# 01_-_Stepper_Motor_Driver.net
KiCad netlist of a schematic drawn in Altium Designer
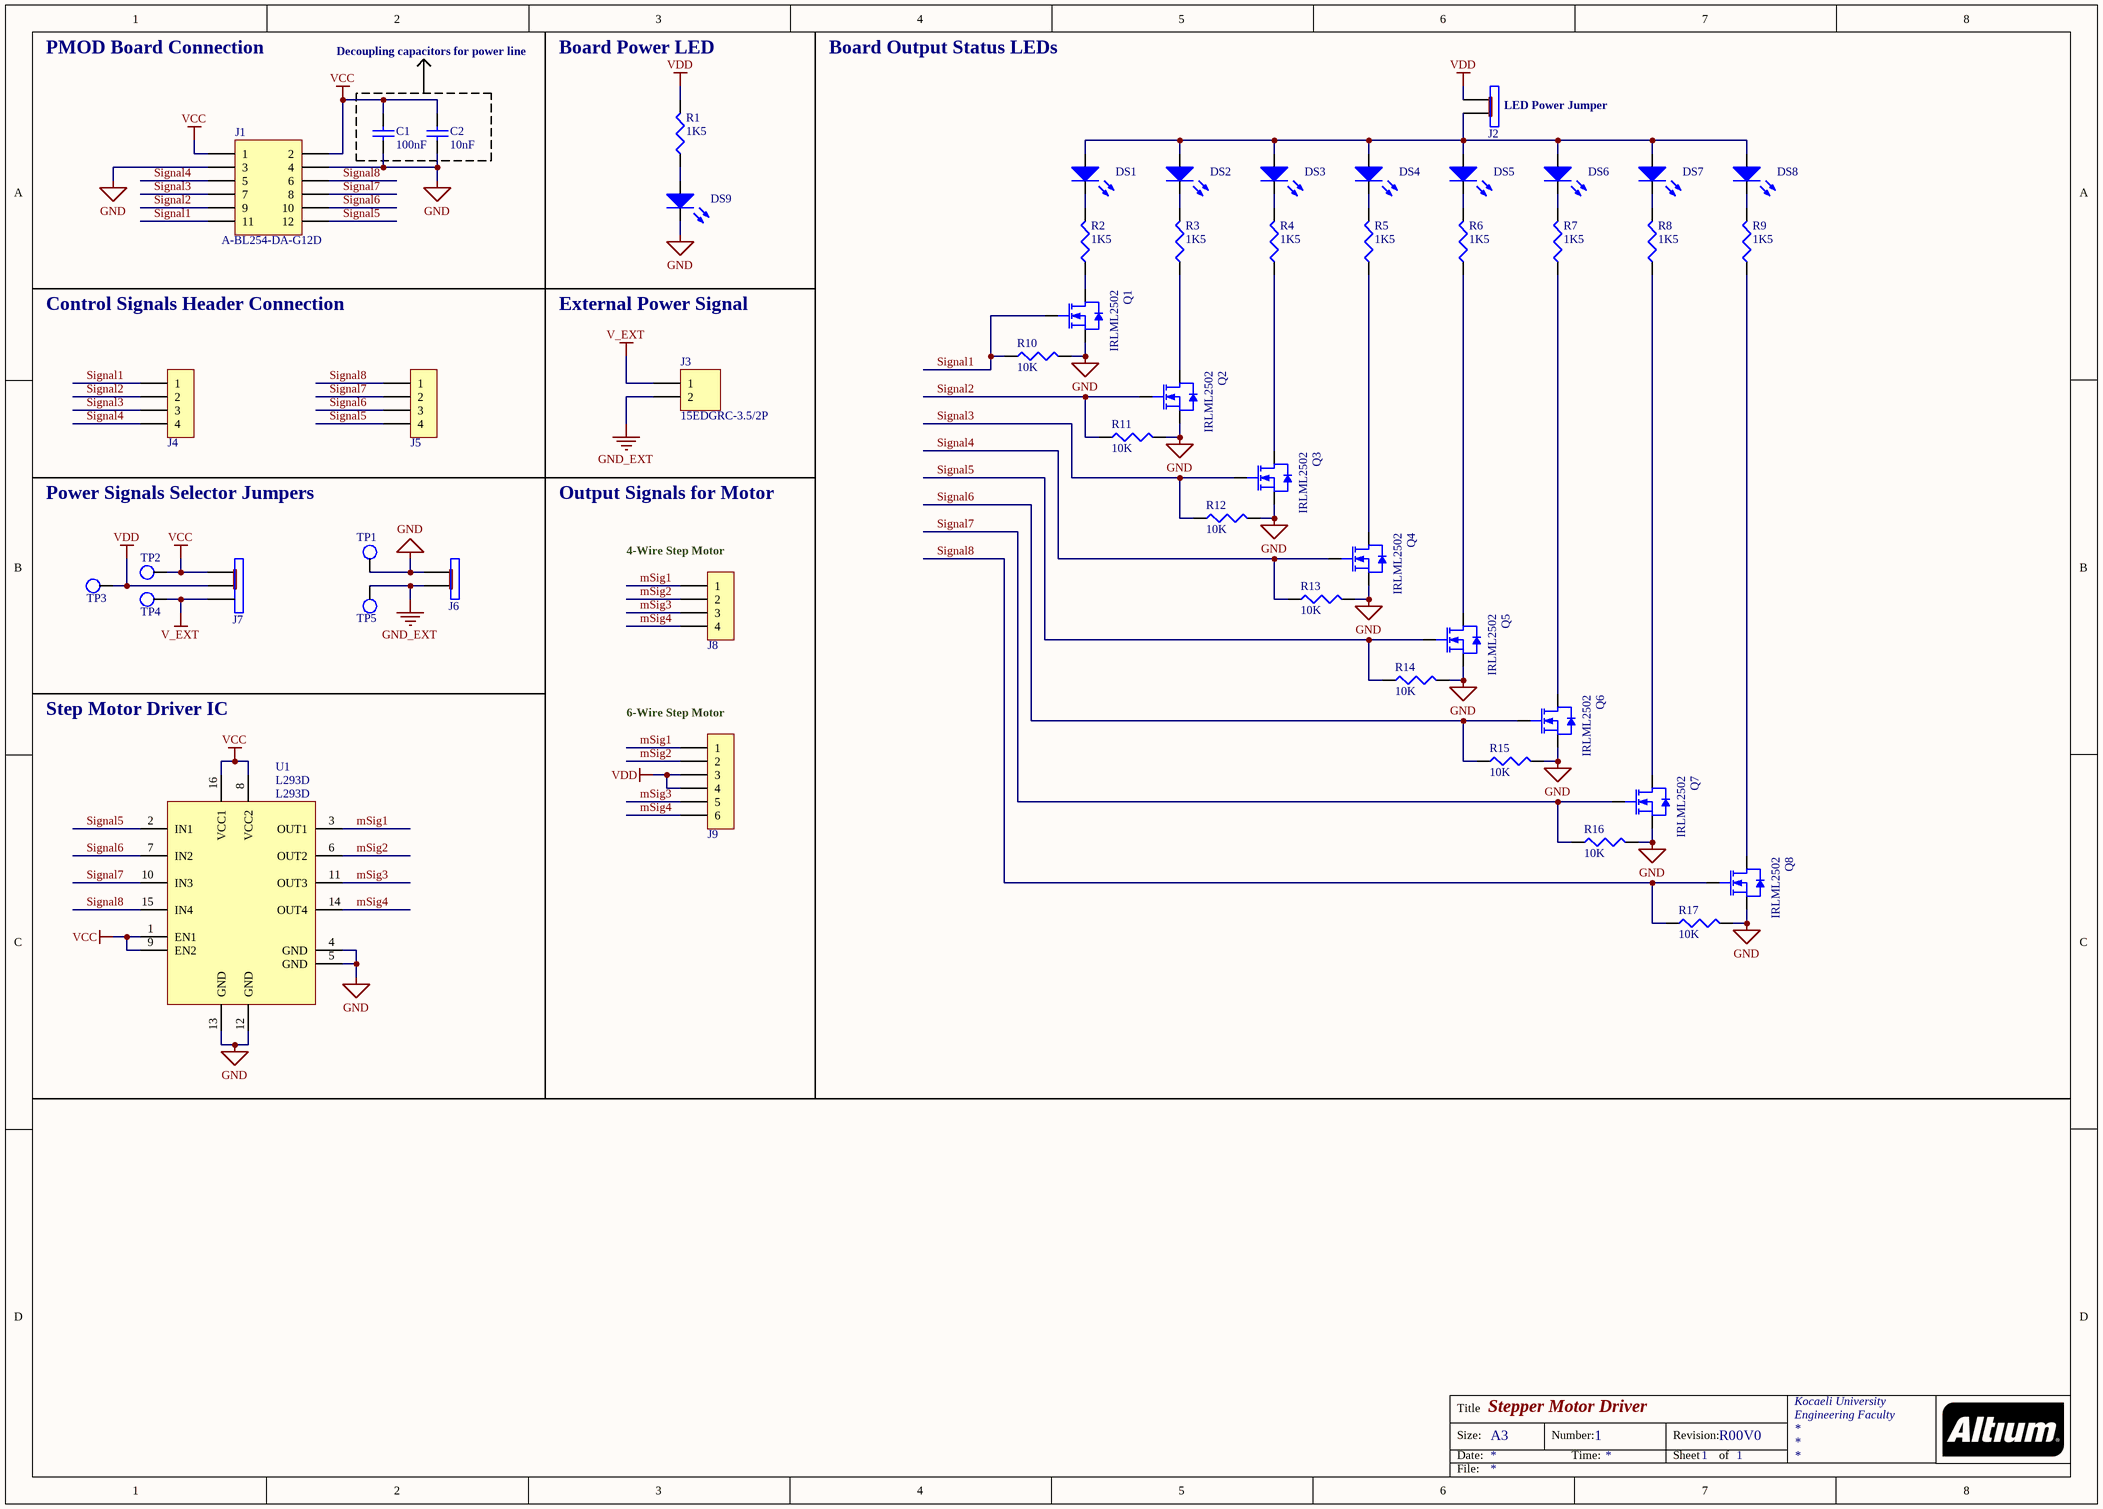
[diagram p0: [01] - Stepper Motor Driver.SchDoc]

(export (version "E")
  (design (tool "Eeschema 10.0.6"))
  (components
    (comp (ref "C1")
      (value "100nF")
      (footprint "CAP-0603")
      (description "CAP CER 0.1UF 50V 10% X7R 0603")
      (fields
        (field (name "MANUFACTURER") "Samsung Electro-Mechanics America, Inc")
        (field (name "MANUFACTURER PART NUMBER") "CL10B104KB8NNNC")
      )
      (libsource (lib "ykLibrary") (part "CAP-100N-0603"))
    )
    (comp (ref "C2")
      (value "10nF")
      (footprint "CAP-0603")
      (description "CAP CER 10000PF 50V 10% X7R 0603")
      (fields
        (field (name "MANUFACTURER") "Samsung Electro-Mechanics America, Inc")
        (field (name "MANUFACTURER PART NUMBER") "CL10B103KB8NNNC")
      )
      (libsource (lib "ykLibrary") (part "CAP-10N-0603"))
    )
    (comp (ref "DS1")
      (value "SMD Green Led")
      (footprint "LED_SMD_0603G")
      (description "LED GREEN CLEAR 0603 SMD")
      (fields
        (field (name "MANUFACTURER") "Lite-On Inc.")
        (field (name "MANUFACTURER PART NUMBER") "LTST-C193KGKT-5A")
      )
      (libsource (lib "ykLibrary") (part "LED-SMD-GRN"))
    )
    (comp (ref "DS2")
      (value "SMD Green Led")
      (footprint "LED_SMD_0603G")
      (description "LED GREEN CLEAR 0603 SMD")
      (fields
        (field (name "MANUFACTURER") "Lite-On Inc.")
        (field (name "MANUFACTURER PART NUMBER") "LTST-C193KGKT-5A")
      )
      (libsource (lib "ykLibrary") (part "LED-SMD-GRN"))
    )
    (comp (ref "DS3")
      (value "SMD Green Led")
      (footprint "LED_SMD_0603G")
      (description "LED GREEN CLEAR 0603 SMD")
      (fields
        (field (name "MANUFACTURER") "Lite-On Inc.")
        (field (name "MANUFACTURER PART NUMBER") "LTST-C193KGKT-5A")
      )
      (libsource (lib "ykLibrary") (part "LED-SMD-GRN"))
    )
    (comp (ref "DS4")
      (value "SMD Green Led")
      (footprint "LED_SMD_0603G")
      (description "LED GREEN CLEAR 0603 SMD")
      (fields
        (field (name "MANUFACTURER") "Lite-On Inc.")
        (field (name "MANUFACTURER PART NUMBER") "LTST-C193KGKT-5A")
      )
      (libsource (lib "ykLibrary") (part "LED-SMD-GRN"))
    )
    (comp (ref "DS5")
      (value "SMD Green Led")
      (footprint "LED_SMD_0603G")
      (description "LED GREEN CLEAR 0603 SMD")
      (fields
        (field (name "MANUFACTURER") "Lite-On Inc.")
        (field (name "MANUFACTURER PART NUMBER") "LTST-C193KGKT-5A")
      )
      (libsource (lib "ykLibrary") (part "LED-SMD-GRN"))
    )
    (comp (ref "DS6")
      (value "SMD Green Led")
      (footprint "LED_SMD_0603G")
      (description "LED GREEN CLEAR 0603 SMD")
      (fields
        (field (name "MANUFACTURER") "Lite-On Inc.")
        (field (name "MANUFACTURER PART NUMBER") "LTST-C193KGKT-5A")
      )
      (libsource (lib "ykLibrary") (part "LED-SMD-GRN"))
    )
    (comp (ref "DS7")
      (value "SMD Green Led")
      (footprint "LED_SMD_0603G")
      (description "LED GREEN CLEAR 0603 SMD")
      (fields
        (field (name "MANUFACTURER") "Lite-On Inc.")
        (field (name "MANUFACTURER PART NUMBER") "LTST-C193KGKT-5A")
      )
      (libsource (lib "ykLibrary") (part "LED-SMD-GRN"))
    )
    (comp (ref "DS8")
      (value "SMD Green Led")
      (footprint "LED_SMD_0603G")
      (description "LED GREEN CLEAR 0603 SMD")
      (fields
        (field (name "MANUFACTURER") "Lite-On Inc.")
        (field (name "MANUFACTURER PART NUMBER") "LTST-C193KGKT-5A")
      )
      (libsource (lib "ykLibrary") (part "LED-SMD-GRN"))
    )
    (comp (ref "DS9")
      (value "SMD Green Led")
      (footprint "LED_SMD_0603G")
      (description "LED GREEN CLEAR 0603 SMD")
      (fields
        (field (name "MANUFACTURER") "Lite-On Inc.")
        (field (name "MANUFACTURER PART NUMBER") "LTST-C193KGKT-5A")
      )
      (libsource (lib "ykLibrary") (part "LED-SMD-GRN"))
    )
    (comp (ref "J1")
      (value "A-BL254-DA-G12D")
      (footprint "CON-PMOD-FEMALE-2X6")
      (description "2.54mm Standart Female PMOD Connector 2x6")
      (fields (field (name "MANUFACTURER") "ASSMANN"))
      (libsource (lib "ykLibrary") (part "CON-PMOD-FEMALE-2X6"))
    )
    (comp (ref "J2")
      (value "2.54mm-Jumper")
      (footprint "CON-JUMPER-2.54-2L")
      (description "2.54mm Male Straight 1x2 standard Header")
      (fields (field (name "MANUFACTURER") "KLS"))
      (libsource (lib "ykLibrary") (part "CON-JUMPER-2.54-2L"))
    )
    (comp (ref "J3")
      (value "15EDGRC-3.5/2P")
      (footprint "15EDGRC-3.5-2")
      (description "Pluggable terminal block; socket; male; angled 90°; 3.5mm; ways:2")
      (fields (field (name "MANUFACTURER") "DEGSON ELECTRONICS"))
      (libsource (lib "ykLibrary") (part "15EDGRC-3.5-02P"))
    )
    (comp (ref "J4")
      (value "2.54mm-STD-M-1x4")
      (footprint "CON-HDR-M-2.54-1x4")
      (description "2.54mm Male Straight 1x2 standard Header")
      (fields (field (name "MANUFACTURER") "KLS"))
      (libsource (lib "ykLibrary") (part "CON-HDR-M-2.54-1x4"))
    )
    (comp (ref "J5")
      (value "2.54mm-STD-M-1x4")
      (footprint "CON-HDR-M-2.54-1x4")
      (description "2.54mm Male Straight 1x2 standard Header")
      (fields (field (name "MANUFACTURER") "KLS"))
      (libsource (lib "ykLibrary") (part "CON-HDR-M-2.54-1x4"))
    )
    (comp (ref "J6")
      (value "2.54mm-Jumper")
      (footprint "CON-JUMPER-2.54-2L")
      (description "2.54mm Male Straight 1x2 standard Header")
      (fields (field (name "MANUFACTURER") "KLS"))
      (libsource (lib "ykLibrary") (part "CON-JUMPER-2.54-2L"))
    )
    (comp (ref "J7")
      (value "2.54mm-Jumper")
      (footprint "CON-JUMPER-2.54-3L")
      (description "2.54mm Male Straight 1x2 standard Header")
      (fields (field (name "MANUFACTURER") "KLS"))
      (libsource (lib "ykLibrary") (part "CON-JUMPER-2.54-3L"))
    )
    (comp (ref "J8")
      (value "L-KLS1-XL5-2.50-04-R1")
      (footprint "CON-JST-XH-2.50-4PIN")
      (description "2.50mm JST-XH 4 Pin Male Connector")
      (fields (field (name "MANUFACTURER") "KLS Electronics"))
      (libsource (lib "ykLibrary") (part "CON-JST-XH-4PIN"))
    )
    (comp (ref "J9")
      (value "L-KLS1-XL5-2.50-06-R1")
      (footprint "CON-JST-XH-2.50-6PIN")
      (description "2.50mm JST-XH 6 Pin Male Connector")
      (fields (field (name "MANUFACTURER") "KLS Electronics"))
      (libsource (lib "ykLibrary") (part "CON-JST-XH-6PIN"))
    )
    (comp (ref "Q1")
      (value "IRLML2502")
      (footprint "SOT23_L")
      (description "MOSFET N-CH 20V 4.2A SOT23")
      (fields
        (field (name "MANUFACTURER") "Infineon Technologies")
        (field (name "MANUFACTURER PART NUMBER") "2N7002K")
      )
      (libsource (lib "ykLibrary") (part "TRQ-IRLML2502"))
    )
    (comp (ref "Q2")
      (value "IRLML2502")
      (footprint "SOT23_L")
      (description "MOSFET N-CH 20V 4.2A SOT23")
      (fields
        (field (name "MANUFACTURER") "Infineon Technologies")
        (field (name "MANUFACTURER PART NUMBER") "2N7002K")
      )
      (libsource (lib "ykLibrary") (part "TRQ-IRLML2502"))
    )
    (comp (ref "Q3")
      (value "IRLML2502")
      (footprint "SOT23_L")
      (description "MOSFET N-CH 20V 4.2A SOT23")
      (fields
        (field (name "MANUFACTURER") "Infineon Technologies")
        (field (name "MANUFACTURER PART NUMBER") "2N7002K")
      )
      (libsource (lib "ykLibrary") (part "TRQ-IRLML2502"))
    )
    (comp (ref "Q4")
      (value "IRLML2502")
      (footprint "SOT23_L")
      (description "MOSFET N-CH 20V 4.2A SOT23")
      (fields
        (field (name "MANUFACTURER") "Infineon Technologies")
        (field (name "MANUFACTURER PART NUMBER") "2N7002K")
      )
      (libsource (lib "ykLibrary") (part "TRQ-IRLML2502"))
    )
    (comp (ref "Q5")
      (value "IRLML2502")
      (footprint "SOT23_L")
      (description "MOSFET N-CH 20V 4.2A SOT23")
      (fields
        (field (name "MANUFACTURER") "Infineon Technologies")
        (field (name "MANUFACTURER PART NUMBER") "2N7002K")
      )
      (libsource (lib "ykLibrary") (part "TRQ-IRLML2502"))
    )
    (comp (ref "Q6")
      (value "IRLML2502")
      (footprint "SOT23_L")
      (description "MOSFET N-CH 20V 4.2A SOT23")
      (fields
        (field (name "MANUFACTURER") "Infineon Technologies")
        (field (name "MANUFACTURER PART NUMBER") "2N7002K")
      )
      (libsource (lib "ykLibrary") (part "TRQ-IRLML2502"))
    )
    (comp (ref "Q7")
      (value "IRLML2502")
      (footprint "SOT23_L")
      (description "MOSFET N-CH 20V 4.2A SOT23")
      (fields
        (field (name "MANUFACTURER") "Infineon Technologies")
        (field (name "MANUFACTURER PART NUMBER") "2N7002K")
      )
      (libsource (lib "ykLibrary") (part "TRQ-IRLML2502"))
    )
    (comp (ref "Q8")
      (value "IRLML2502")
      (footprint "SOT23_L")
      (description "MOSFET N-CH 20V 4.2A SOT23")
      (fields
        (field (name "MANUFACTURER") "Infineon Technologies")
        (field (name "MANUFACTURER PART NUMBER") "2N7002K")
      )
      (libsource (lib "ykLibrary") (part "TRQ-IRLML2502"))
    )
    (comp (ref "R1")
      (value "1K5")
      (footprint "RES-0603")
      (description "RES 1.5K OHM 1% 1/10W 0603")
      (fields
        (field (name "MANUFACTURER") "YAGEO")
        (field (name "MANUFACTURER PART NUMBER") "RC0603FR-131K5L")
      )
      (libsource (lib "ykLibrary") (part "RES-1K5-0603"))
    )
    (comp (ref "R2")
      (value "1K5")
      (footprint "RES-0603")
      (description "RES 1.5K OHM 1% 1/10W 0603")
      (fields
        (field (name "MANUFACTURER") "YAGEO")
        (field (name "MANUFACTURER PART NUMBER") "RC0603FR-131K5L")
      )
      (libsource (lib "ykLibrary") (part "RES-1K5-0603"))
    )
    (comp (ref "R3")
      (value "1K5")
      (footprint "RES-0603")
      (description "RES 1.5K OHM 1% 1/10W 0603")
      (fields
        (field (name "MANUFACTURER") "YAGEO")
        (field (name "MANUFACTURER PART NUMBER") "RC0603FR-131K5L")
      )
      (libsource (lib "ykLibrary") (part "RES-1K5-0603"))
    )
    (comp (ref "R4")
      (value "1K5")
      (footprint "RES-0603")
      (description "RES 1.5K OHM 1% 1/10W 0603")
      (fields
        (field (name "MANUFACTURER") "YAGEO")
        (field (name "MANUFACTURER PART NUMBER") "RC0603FR-131K5L")
      )
      (libsource (lib "ykLibrary") (part "RES-1K5-0603"))
    )
    (comp (ref "R5")
      (value "1K5")
      (footprint "RES-0603")
      (description "RES 1.5K OHM 1% 1/10W 0603")
      (fields
        (field (name "MANUFACTURER") "YAGEO")
        (field (name "MANUFACTURER PART NUMBER") "RC0603FR-131K5L")
      )
      (libsource (lib "ykLibrary") (part "RES-1K5-0603"))
    )
    (comp (ref "R6")
      (value "1K5")
      (footprint "RES-0603")
      (description "RES 1.5K OHM 1% 1/10W 0603")
      (fields
        (field (name "MANUFACTURER") "YAGEO")
        (field (name "MANUFACTURER PART NUMBER") "RC0603FR-131K5L")
      )
      (libsource (lib "ykLibrary") (part "RES-1K5-0603"))
    )
    (comp (ref "R7")
      (value "1K5")
      (footprint "RES-0603")
      (description "RES 1.5K OHM 1% 1/10W 0603")
      (fields
        (field (name "MANUFACTURER") "YAGEO")
        (field (name "MANUFACTURER PART NUMBER") "RC0603FR-131K5L")
      )
      (libsource (lib "ykLibrary") (part "RES-1K5-0603"))
    )
    (comp (ref "R8")
      (value "1K5")
      (footprint "RES-0603")
      (description "RES 1.5K OHM 1% 1/10W 0603")
      (fields
        (field (name "MANUFACTURER") "YAGEO")
        (field (name "MANUFACTURER PART NUMBER") "RC0603FR-131K5L")
      )
      (libsource (lib "ykLibrary") (part "RES-1K5-0603"))
    )
    (comp (ref "R9")
      (value "1K5")
      (footprint "RES-0603")
      (description "RES 1.5K OHM 1% 1/10W 0603")
      (fields
        (field (name "MANUFACTURER") "YAGEO")
        (field (name "MANUFACTURER PART NUMBER") "RC0603FR-131K5L")
      )
      (libsource (lib "ykLibrary") (part "RES-1K5-0603"))
    )
    (comp (ref "R10")
      (value "10K")
      (footprint "RES-0603")
      (description "RES 10K OHM 1% 1/10W 0603")
      (fields
        (field (name "MANUFACTURER") "YAGEO")
        (field (name "MANUFACTURER PART NUMBER") "RC0603FR-1310KL")
      )
      (libsource (lib "ykLibrary") (part "RES-10K-0603"))
    )
    (comp (ref "R11")
      (value "10K")
      (footprint "RES-0603")
      (description "RES 10K OHM 1% 1/10W 0603")
      (fields
        (field (name "MANUFACTURER") "YAGEO")
        (field (name "MANUFACTURER PART NUMBER") "RC0603FR-1310KL")
      )
      (libsource (lib "ykLibrary") (part "RES-10K-0603"))
    )
    (comp (ref "R12")
      (value "10K")
      (footprint "RES-0603")
      (description "RES 10K OHM 1% 1/10W 0603")
      (fields
        (field (name "MANUFACTURER") "YAGEO")
        (field (name "MANUFACTURER PART NUMBER") "RC0603FR-1310KL")
      )
      (libsource (lib "ykLibrary") (part "RES-10K-0603"))
    )
    (comp (ref "R13")
      (value "10K")
      (footprint "RES-0603")
      (description "RES 10K OHM 1% 1/10W 0603")
      (fields
        (field (name "MANUFACTURER") "YAGEO")
        (field (name "MANUFACTURER PART NUMBER") "RC0603FR-1310KL")
      )
      (libsource (lib "ykLibrary") (part "RES-10K-0603"))
    )
    (comp (ref "R14")
      (value "10K")
      (footprint "RES-0603")
      (description "RES 10K OHM 1% 1/10W 0603")
      (fields
        (field (name "MANUFACTURER") "YAGEO")
        (field (name "MANUFACTURER PART NUMBER") "RC0603FR-1310KL")
      )
      (libsource (lib "ykLibrary") (part "RES-10K-0603"))
    )
    (comp (ref "R15")
      (value "10K")
      (footprint "RES-0603")
      (description "RES 10K OHM 1% 1/10W 0603")
      (fields
        (field (name "MANUFACTURER") "YAGEO")
        (field (name "MANUFACTURER PART NUMBER") "RC0603FR-1310KL")
      )
      (libsource (lib "ykLibrary") (part "RES-10K-0603"))
    )
    (comp (ref "R16")
      (value "10K")
      (footprint "RES-0603")
      (description "RES 10K OHM 1% 1/10W 0603")
      (fields
        (field (name "MANUFACTURER") "YAGEO")
        (field (name "MANUFACTURER PART NUMBER") "RC0603FR-1310KL")
      )
      (libsource (lib "ykLibrary") (part "RES-10K-0603"))
    )
    (comp (ref "R17")
      (value "10K")
      (footprint "RES-0603")
      (description "RES 10K OHM 1% 1/10W 0603")
      (fields
        (field (name "MANUFACTURER") "YAGEO")
        (field (name "MANUFACTURER PART NUMBER") "RC0603FR-1310KL")
      )
      (libsource (lib "ykLibrary") (part "RES-10K-0603"))
    )
    (comp (ref "TP1")
      (value "TP")
      (footprint "TP_TH")
      (description "Test Point")
      (fields (field (name "PUBLISHER") "tmk"))
      (libsource (lib "ykLibrary") (part "TP"))
    )
    (comp (ref "TP2")
      (value "TP")
      (footprint "TP_TH")
      (description "Test Point")
      (fields (field (name "PUBLISHER") "tmk"))
      (libsource (lib "ykLibrary") (part "TP"))
    )
    (comp (ref "TP3")
      (value "TP")
      (footprint "TP_TH")
      (description "Test Point")
      (fields (field (name "PUBLISHER") "tmk"))
      (libsource (lib "ykLibrary") (part "TP"))
    )
    (comp (ref "TP4")
      (value "TP")
      (footprint "TP_TH")
      (description "Test Point")
      (fields (field (name "PUBLISHER") "tmk"))
      (libsource (lib "ykLibrary") (part "TP"))
    )
    (comp (ref "TP5")
      (value "TP")
      (footprint "TP_TH")
      (description "Test Point")
      (fields (field (name "PUBLISHER") "tmk"))
      (libsource (lib "ykLibrary") (part "TP"))
    )
    (comp (ref "U1")
      (value "L293D")
      (footprint "PDIP-16")
      (description "IC MTR DRV BIPOLR 4.5-36V 20SOIC")
      (fields (field (name "ALTIUM_VALUE") "L293D"))
      (libsource (lib "ykLibrary") (part "IC-L293D-PDIP"))
    )
  )
  (nets
    (net (code "1") (name "/Signal1") (class "Default")
      (node (ref "J1") (pin "11") (pinfunction "11_11") (pintype "passive"))
      (node (ref "J4") (pin "1") (pinfunction "1_1") (pintype "passive"))
      (node (ref "Q1") (pin "1") (pinfunction "G_1") (pintype "passive"))
      (node (ref "R10") (pin "1") (pinfunction "1_1") (pintype "passive"))
    )
    (net (code "2") (name "/Signal2") (class "Default")
      (node (ref "J1") (pin "9") (pinfunction "9_9") (pintype "passive"))
      (node (ref "J4") (pin "2") (pinfunction "2_2") (pintype "passive"))
      (node (ref "Q2") (pin "1") (pinfunction "G_1") (pintype "passive"))
      (node (ref "R11") (pin "1") (pinfunction "1_1") (pintype "passive"))
    )
    (net (code "3") (name "/Signal3") (class "Default")
      (node (ref "J1") (pin "7") (pinfunction "7_7") (pintype "passive"))
      (node (ref "J4") (pin "3") (pinfunction "3_3") (pintype "passive"))
      (node (ref "Q3") (pin "1") (pinfunction "G_1") (pintype "passive"))
      (node (ref "R12") (pin "1") (pinfunction "1_1") (pintype "passive"))
    )
    (net (code "4") (name "/Signal4") (class "Default")
      (node (ref "J1") (pin "5") (pinfunction "5_5") (pintype "passive"))
      (node (ref "J4") (pin "4") (pinfunction "4_4") (pintype "passive"))
      (node (ref "Q4") (pin "1") (pinfunction "G_1") (pintype "passive"))
      (node (ref "R13") (pin "1") (pinfunction "1_1") (pintype "passive"))
    )
    (net (code "5") (name "/Signal5") (class "Default")
      (node (ref "J1") (pin "12") (pinfunction "12_12") (pintype "passive"))
      (node (ref "J5") (pin "4") (pinfunction "4_4") (pintype "passive"))
      (node (ref "Q5") (pin "1") (pinfunction "G_1") (pintype "passive"))
      (node (ref "R14") (pin "1") (pinfunction "1_1") (pintype "passive"))
      (node (ref "U1") (pin "2") (pinfunction "IN1_2") (pintype "passive"))
    )
    (net (code "6") (name "/Signal6") (class "Default")
      (node (ref "J1") (pin "10") (pinfunction "10_10") (pintype "passive"))
      (node (ref "J5") (pin "3") (pinfunction "3_3") (pintype "passive"))
      (node (ref "Q6") (pin "1") (pinfunction "G_1") (pintype "passive"))
      (node (ref "R15") (pin "1") (pinfunction "1_1") (pintype "passive"))
      (node (ref "U1") (pin "7") (pinfunction "IN2_7") (pintype "passive"))
    )
    (net (code "7") (name "/Signal7") (class "Default")
      (node (ref "J1") (pin "8") (pinfunction "8_8") (pintype "passive"))
      (node (ref "J5") (pin "2") (pinfunction "2_2") (pintype "passive"))
      (node (ref "Q7") (pin "1") (pinfunction "G_1") (pintype "passive"))
      (node (ref "R16") (pin "1") (pinfunction "1_1") (pintype "passive"))
      (node (ref "U1") (pin "10") (pinfunction "IN3_10") (pintype "passive"))
    )
    (net (code "8") (name "/Signal8") (class "Default")
      (node (ref "J1") (pin "6") (pinfunction "6_6") (pintype "passive"))
      (node (ref "J5") (pin "1") (pinfunction "1_1") (pintype "passive"))
      (node (ref "Q8") (pin "1") (pinfunction "G_1") (pintype "passive"))
      (node (ref "R17") (pin "1") (pinfunction "1_1") (pintype "passive"))
      (node (ref "U1") (pin "15") (pinfunction "IN4_15") (pintype "passive"))
    )
    (net (code "9") (name "/mSig1") (class "Default")
      (node (ref "J8") (pin "1") (pinfunction "1_1") (pintype "passive"))
      (node (ref "J9") (pin "1") (pinfunction "1_1") (pintype "passive"))
      (node (ref "U1") (pin "3") (pinfunction "OUT1_3") (pintype "passive"))
    )
    (net (code "10") (name "/mSig2") (class "Default")
      (node (ref "J8") (pin "2") (pinfunction "2_2") (pintype "passive"))
      (node (ref "J9") (pin "2") (pinfunction "2_2") (pintype "passive"))
      (node (ref "U1") (pin "6") (pinfunction "OUT2_6") (pintype "passive"))
    )
    (net (code "11") (name "/mSig3") (class "Default")
      (node (ref "J8") (pin "3") (pinfunction "3_3") (pintype "passive"))
      (node (ref "J9") (pin "5") (pinfunction "5_5") (pintype "passive"))
      (node (ref "U1") (pin "11") (pinfunction "OUT3_11") (pintype "passive"))
    )
    (net (code "12") (name "/mSig4") (class "Default")
      (node (ref "J8") (pin "4") (pinfunction "4_4") (pintype "passive"))
      (node (ref "J9") (pin "6") (pinfunction "6_6") (pintype "passive"))
      (node (ref "U1") (pin "14") (pinfunction "OUT4_14") (pintype "passive"))
    )
    (net (code "13") (name "GND") (class "Default")
      (node (ref "C1") (pin "1") (pinfunction "1_1") (pintype "passive"))
      (node (ref "C2") (pin "1") (pinfunction "1_1") (pintype "passive"))
      (node (ref "DS9") (pin "2") (pinfunction "K_2") (pintype "passive"))
      (node (ref "J1") (pin "3") (pinfunction "3_3") (pintype "passive"))
      (node (ref "J1") (pin "4") (pinfunction "4_4") (pintype "passive"))
      (node (ref "J6") (pin "1") (pinfunction "1_1") (pintype "passive"))
      (node (ref "Q1") (pin "2") (pinfunction "S_2") (pintype "passive"))
      (node (ref "Q2") (pin "2") (pinfunction "S_2") (pintype "passive"))
      (node (ref "Q3") (pin "2") (pinfunction "S_2") (pintype "passive"))
      (node (ref "Q4") (pin "2") (pinfunction "S_2") (pintype "passive"))
      (node (ref "Q5") (pin "2") (pinfunction "S_2") (pintype "passive"))
      (node (ref "Q6") (pin "2") (pinfunction "S_2") (pintype "passive"))
      (node (ref "Q7") (pin "2") (pinfunction "S_2") (pintype "passive"))
      (node (ref "Q8") (pin "2") (pinfunction "S_2") (pintype "passive"))
      (node (ref "R10") (pin "2") (pinfunction "2_2") (pintype "passive"))
      (node (ref "R11") (pin "2") (pinfunction "2_2") (pintype "passive"))
      (node (ref "R12") (pin "2") (pinfunction "2_2") (pintype "passive"))
      (node (ref "R13") (pin "2") (pinfunction "2_2") (pintype "passive"))
      (node (ref "R14") (pin "2") (pinfunction "2_2") (pintype "passive"))
      (node (ref "R15") (pin "2") (pinfunction "2_2") (pintype "passive"))
      (node (ref "R16") (pin "2") (pinfunction "2_2") (pintype "passive"))
      (node (ref "R17") (pin "2") (pinfunction "2_2") (pintype "passive"))
      (node (ref "TP1") (pin "0") (pinfunction "0_0") (pintype "passive"))
      (node (ref "U1") (pin "12") (pinfunction "GND_12") (pintype "passive"))
      (node (ref "U1") (pin "13") (pinfunction "GND_13") (pintype "passive"))
      (node (ref "U1") (pin "4") (pinfunction "GND_4") (pintype "passive"))
      (node (ref "U1") (pin "5") (pinfunction "GND_5") (pintype "passive"))
    )
    (net (code "14") (name "GND_EXT") (class "Default")
      (node (ref "J3") (pin "2") (pinfunction "2_2") (pintype "passive"))
      (node (ref "J6") (pin "2") (pinfunction "2_2") (pintype "passive"))
      (node (ref "TP5") (pin "0") (pinfunction "0_0") (pintype "passive"))
    )
    (net (code "15") (name "Net-(DS1-A)") (class "Default")
      (node (ref "DS1") (pin "1") (pinfunction "A_1") (pintype "passive"))
      (node (ref "DS2") (pin "1") (pinfunction "A_1") (pintype "passive"))
      (node (ref "DS3") (pin "1") (pinfunction "A_1") (pintype "passive"))
      (node (ref "DS4") (pin "1") (pinfunction "A_1") (pintype "passive"))
      (node (ref "DS5") (pin "1") (pinfunction "A_1") (pintype "passive"))
      (node (ref "DS6") (pin "1") (pinfunction "A_1") (pintype "passive"))
      (node (ref "DS7") (pin "1") (pinfunction "A_1") (pintype "passive"))
      (node (ref "DS8") (pin "1") (pinfunction "A_1") (pintype "passive"))
      (node (ref "J2") (pin "2") (pinfunction "2_2") (pintype "passive"))
    )
    (net (code "16") (name "Net-(DS1-K)") (class "Default")
      (node (ref "DS1") (pin "2") (pinfunction "K_2") (pintype "passive"))
      (node (ref "R2") (pin "2") (pinfunction "2_2") (pintype "passive"))
    )
    (net (code "17") (name "Net-(DS2-K)") (class "Default")
      (node (ref "DS2") (pin "2") (pinfunction "K_2") (pintype "passive"))
      (node (ref "R3") (pin "2") (pinfunction "2_2") (pintype "passive"))
    )
    (net (code "18") (name "Net-(DS3-K)") (class "Default")
      (node (ref "DS3") (pin "2") (pinfunction "K_2") (pintype "passive"))
      (node (ref "R4") (pin "2") (pinfunction "2_2") (pintype "passive"))
    )
    (net (code "19") (name "Net-(DS4-K)") (class "Default")
      (node (ref "DS4") (pin "2") (pinfunction "K_2") (pintype "passive"))
      (node (ref "R5") (pin "2") (pinfunction "2_2") (pintype "passive"))
    )
    (net (code "20") (name "Net-(DS5-K)") (class "Default")
      (node (ref "DS5") (pin "2") (pinfunction "K_2") (pintype "passive"))
      (node (ref "R6") (pin "2") (pinfunction "2_2") (pintype "passive"))
    )
    (net (code "21") (name "Net-(DS6-K)") (class "Default")
      (node (ref "DS6") (pin "2") (pinfunction "K_2") (pintype "passive"))
      (node (ref "R7") (pin "2") (pinfunction "2_2") (pintype "passive"))
    )
    (net (code "22") (name "Net-(DS7-K)") (class "Default")
      (node (ref "DS7") (pin "2") (pinfunction "K_2") (pintype "passive"))
      (node (ref "R8") (pin "2") (pinfunction "2_2") (pintype "passive"))
    )
    (net (code "23") (name "Net-(DS8-K)") (class "Default")
      (node (ref "DS8") (pin "2") (pinfunction "K_2") (pintype "passive"))
      (node (ref "R9") (pin "2") (pinfunction "2_2") (pintype "passive"))
    )
    (net (code "24") (name "Net-(DS9-A)") (class "Default")
      (node (ref "DS9") (pin "1") (pinfunction "A_1") (pintype "passive"))
      (node (ref "R1") (pin "1") (pinfunction "1_1") (pintype "passive"))
    )
    (net (code "25") (name "Net-(Q1-D)") (class "Default")
      (node (ref "Q1") (pin "3") (pinfunction "D_3") (pintype "passive"))
      (node (ref "R2") (pin "1") (pinfunction "1_1") (pintype "passive"))
    )
    (net (code "26") (name "Net-(Q2-D)") (class "Default")
      (node (ref "Q2") (pin "3") (pinfunction "D_3") (pintype "passive"))
      (node (ref "R3") (pin "1") (pinfunction "1_1") (pintype "passive"))
    )
    (net (code "27") (name "Net-(Q3-D)") (class "Default")
      (node (ref "Q3") (pin "3") (pinfunction "D_3") (pintype "passive"))
      (node (ref "R4") (pin "1") (pinfunction "1_1") (pintype "passive"))
    )
    (net (code "28") (name "Net-(Q4-D)") (class "Default")
      (node (ref "Q4") (pin "3") (pinfunction "D_3") (pintype "passive"))
      (node (ref "R5") (pin "1") (pinfunction "1_1") (pintype "passive"))
    )
    (net (code "29") (name "Net-(Q5-D)") (class "Default")
      (node (ref "Q5") (pin "3") (pinfunction "D_3") (pintype "passive"))
      (node (ref "R6") (pin "1") (pinfunction "1_1") (pintype "passive"))
    )
    (net (code "30") (name "Net-(Q6-D)") (class "Default")
      (node (ref "Q6") (pin "3") (pinfunction "D_3") (pintype "passive"))
      (node (ref "R7") (pin "1") (pinfunction "1_1") (pintype "passive"))
    )
    (net (code "31") (name "Net-(Q7-D)") (class "Default")
      (node (ref "Q7") (pin "3") (pinfunction "D_3") (pintype "passive"))
      (node (ref "R8") (pin "1") (pinfunction "1_1") (pintype "passive"))
    )
    (net (code "32") (name "Net-(Q8-D)") (class "Default")
      (node (ref "Q8") (pin "3") (pinfunction "D_3") (pintype "passive"))
      (node (ref "R9") (pin "1") (pinfunction "1_1") (pintype "passive"))
    )
    (net (code "33") (name "VCC") (class "Default")
      (node (ref "C1") (pin "2") (pinfunction "2_2") (pintype "passive"))
      (node (ref "C2") (pin "2") (pinfunction "2_2") (pintype "passive"))
      (node (ref "J1") (pin "1") (pinfunction "1_1") (pintype "passive"))
      (node (ref "J1") (pin "2") (pinfunction "2_2") (pintype "passive"))
      (node (ref "J7") (pin "1") (pinfunction "1_1") (pintype "passive"))
      (node (ref "TP2") (pin "0") (pinfunction "0_0") (pintype "passive"))
      (node (ref "U1") (pin "1") (pinfunction "EN1_1") (pintype "passive"))
      (node (ref "U1") (pin "16") (pinfunction "VCC1_16") (pintype "passive"))
      (node (ref "U1") (pin "8") (pinfunction "VCC2_8") (pintype "passive"))
      (node (ref "U1") (pin "9") (pinfunction "EN2_9") (pintype "passive"))
    )
    (net (code "34") (name "VDD") (class "Default")
      (node (ref "J2") (pin "1") (pinfunction "1_1") (pintype "passive"))
      (node (ref "J7") (pin "2") (pinfunction "2_2") (pintype "passive"))
      (node (ref "J9") (pin "3") (pinfunction "3_3") (pintype "passive"))
      (node (ref "J9") (pin "4") (pinfunction "4_4") (pintype "passive"))
      (node (ref "R1") (pin "2") (pinfunction "2_2") (pintype "passive"))
      (node (ref "TP3") (pin "0") (pinfunction "0_0") (pintype "passive"))
    )
    (net (code "35") (name "V_EXT") (class "Default")
      (node (ref "J3") (pin "1") (pinfunction "1_1") (pintype "passive"))
      (node (ref "J7") (pin "3") (pinfunction "3_3") (pintype "passive"))
      (node (ref "TP4") (pin "0") (pinfunction "0_0") (pintype "passive"))
    )
  )
)
